# avrusbboot_example.net
KiCad netlist of a schematic drawn in EAGLE
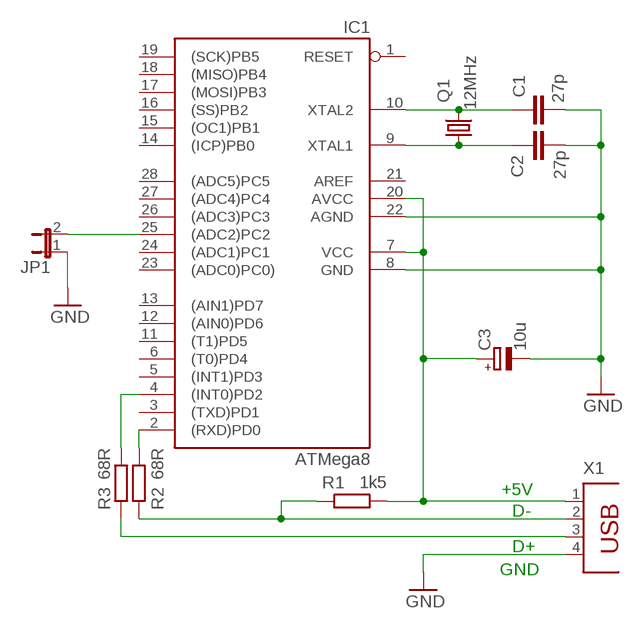
[diagram p0: schematic, sheet 1]

(export (version "E")
  (design (tool "Eeschema 10.0.6"))
  (components
    (comp (ref "C1")
      (value "27p")
      (footprint "eagle-import:C025-024X044")
      (libsource (lib "eagle-import") (part "C-EU025-024X044"))
    )
    (comp (ref "C2")
      (value "27p")
      (footprint "eagle-import:C025-024X044")
      (libsource (lib "eagle-import") (part "C-EU025-024X044"))
    )
    (comp (ref "C3")
      (value "10u")
      (footprint "eagle-import:E2,5-5")
      (libsource (lib "eagle-import") (part "CPOL-EUE2.5-5"))
    )
    (comp (ref "IC1")
      (value "ATMega8")
      (footprint "eagle-import:DIL28-3")
      (libsource (lib "eagle-import") (part "AT90S4433P"))
    )
    (comp (ref "JP1")
      (value "JP1E")
      (footprint "eagle-import:JP1")
      (libsource (lib "eagle-import") (part "JP1E"))
    )
    (comp (ref "Q1")
      (value "12MHz")
      (footprint "eagle-import:HC49_S")
      (libsource (lib "eagle-import") (part "CRYTALHC49S"))
    )
    (comp (ref "R1")
      (value "1k5")
      (footprint "eagle-import:0207_7")
      (libsource (lib "eagle-import") (part "R-EU_0207/7"))
    )
    (comp (ref "R2")
      (value "68R")
      (footprint "eagle-import:0207_7")
      (libsource (lib "eagle-import") (part "R-EU_0207/7"))
    )
    (comp (ref "R3")
      (value "68R")
      (footprint "eagle-import:0207_7")
      (libsource (lib "eagle-import") (part "R-EU_0207/7"))
    )
    (comp (ref "X1")
      (value "PN61729")
      (footprint "eagle-import:PN61729")
      (libsource (lib "eagle-import") (part "PN61729"))
    )
  )
  (nets
    (net (code "1") (name "/AREF") (class "Default")
      (node (ref "IC1") (pin "21") (pinfunction "AREF_21") (pintype "power_in"))
    )
    (net (code "2") (name "GND") (class "Default")
      (node (ref "C1") (pin "2") (pinfunction "2_2") (pintype "passive"))
      (node (ref "C2") (pin "2") (pinfunction "2_2") (pintype "passive"))
      (node (ref "C3") (pin "-") (pinfunction "-_-") (pintype "passive"))
      (node (ref "IC1") (pin "22") (pinfunction "AGND_22") (pintype "power_in"))
      (node (ref "IC1") (pin "8") (pinfunction "GND_8") (pintype "power_in"))
      (node (ref "JP1") (pin "1") (pinfunction "1_1") (pintype "passive"))
      (node (ref "X1") (pin "4") (pinfunction "4_4") (pintype "bidirectional"))
    )
    (net (code "3") (name "Net-(IC1-(ADC2)PC2)") (class "Default")
      (node (ref "IC1") (pin "25") (pinfunction "(ADC2)PC2_25") (pintype "bidirectional"))
      (node (ref "JP1") (pin "2") (pinfunction "2_2") (pintype "passive"))
    )
    (net (code "4") (name "Net-(IC1-(INT0)PD2)") (class "Default")
      (node (ref "IC1") (pin "4") (pinfunction "(INT0)PD2_4") (pintype "bidirectional"))
      (node (ref "R3") (pin "2") (pinfunction "2_2") (pintype "passive"))
    )
    (net (code "5") (name "Net-(IC1-(RXD)PD0)") (class "Default")
      (node (ref "IC1") (pin "2") (pinfunction "(RXD)PD0_2") (pintype "bidirectional"))
      (node (ref "R2") (pin "2") (pinfunction "2_2") (pintype "passive"))
    )
    (net (code "6") (name "Net-(IC1-AVCC)") (class "Default")
      (node (ref "C3") (pin "+") (pinfunction "+_+") (pintype "passive"))
      (node (ref "IC1") (pin "20") (pinfunction "AVCC_20") (pintype "power_in"))
      (node (ref "IC1") (pin "7") (pinfunction "VCC_7") (pintype "power_in"))
      (node (ref "R1") (pin "2") (pinfunction "2_2") (pintype "passive"))
      (node (ref "X1") (pin "1") (pinfunction "1_1") (pintype "bidirectional"))
    )
    (net (code "7") (name "Net-(IC1-XTAL1)") (class "Default")
      (node (ref "C2") (pin "1") (pinfunction "1_1") (pintype "passive"))
      (node (ref "IC1") (pin "9") (pinfunction "XTAL1_9") (pintype "bidirectional"))
      (node (ref "Q1") (pin "1") (pinfunction "1_1") (pintype "passive"))
    )
    (net (code "8") (name "Net-(IC1-XTAL2)") (class "Default")
      (node (ref "C1") (pin "1") (pinfunction "1_1") (pintype "passive"))
      (node (ref "IC1") (pin "10") (pinfunction "XTAL2_10") (pintype "bidirectional"))
      (node (ref "Q1") (pin "2") (pinfunction "2_2") (pintype "passive"))
    )
    (net (code "9") (name "Net-(R1-Pad1)") (class "Default")
      (node (ref "R1") (pin "1") (pinfunction "1_1") (pintype "passive"))
      (node (ref "R2") (pin "1") (pinfunction "1_1") (pintype "passive"))
      (node (ref "X1") (pin "2") (pinfunction "2_2") (pintype "bidirectional"))
    )
    (net (code "10") (name "Net-(R3-Pad1)") (class "Default")
      (node (ref "R3") (pin "1") (pinfunction "1_1") (pintype "passive"))
      (node (ref "X1") (pin "3") (pinfunction "3_3") (pintype "bidirectional"))
    )
    (net (code "11") (name "unconnected-(IC1-(ADC0)PC0)-Pad23)") (class "Default")
      (node (ref "IC1") (pin "23") (pinfunction "(ADC0)PC0)_23") (pintype "bidirectional"))
    )
    (net (code "12") (name "unconnected-(IC1-(ADC1)PC1-Pad24)") (class "Default")
      (node (ref "IC1") (pin "24") (pinfunction "(ADC1)PC1_24") (pintype "bidirectional"))
    )
    (net (code "13") (name "unconnected-(IC1-(ADC3)PC3-Pad26)") (class "Default")
      (node (ref "IC1") (pin "26") (pinfunction "(ADC3)PC3_26") (pintype "bidirectional"))
    )
    (net (code "14") (name "unconnected-(IC1-(ADC4)PC4-Pad27)") (class "Default")
      (node (ref "IC1") (pin "27") (pinfunction "(ADC4)PC4_27") (pintype "bidirectional"))
    )
    (net (code "15") (name "unconnected-(IC1-(ADC5)PC5-Pad28)") (class "Default")
      (node (ref "IC1") (pin "28") (pinfunction "(ADC5)PC5_28") (pintype "bidirectional"))
    )
    (net (code "16") (name "unconnected-(IC1-(AIN0)PD6-Pad12)") (class "Default")
      (node (ref "IC1") (pin "12") (pinfunction "(AIN0)PD6_12") (pintype "bidirectional"))
    )
    (net (code "17") (name "unconnected-(IC1-(AIN1)PD7-Pad13)") (class "Default")
      (node (ref "IC1") (pin "13") (pinfunction "(AIN1)PD7_13") (pintype "bidirectional"))
    )
    (net (code "18") (name "unconnected-(IC1-(ICP)PB0-Pad14)") (class "Default")
      (node (ref "IC1") (pin "14") (pinfunction "(ICP)PB0_14") (pintype "bidirectional"))
    )
    (net (code "19") (name "unconnected-(IC1-(INT1)PD3-Pad5)") (class "Default")
      (node (ref "IC1") (pin "5") (pinfunction "(INT1)PD3_5") (pintype "bidirectional"))
    )
    (net (code "20") (name "unconnected-(IC1-(MISO)PB4-Pad18)") (class "Default")
      (node (ref "IC1") (pin "18") (pinfunction "(MISO)PB4_18") (pintype "bidirectional"))
    )
    (net (code "21") (name "unconnected-(IC1-(MOSI)PB3-Pad17)") (class "Default")
      (node (ref "IC1") (pin "17") (pinfunction "(MOSI)PB3_17") (pintype "bidirectional"))
    )
    (net (code "22") (name "unconnected-(IC1-(OC1)PB1-Pad15)") (class "Default")
      (node (ref "IC1") (pin "15") (pinfunction "(OC1)PB1_15") (pintype "bidirectional"))
    )
    (net (code "23") (name "unconnected-(IC1-(SCK)PB5-Pad19)") (class "Default")
      (node (ref "IC1") (pin "19") (pinfunction "(SCK)PB5_19") (pintype "bidirectional"))
    )
    (net (code "24") (name "unconnected-(IC1-(SS)PB2-Pad16)") (class "Default")
      (node (ref "IC1") (pin "16") (pinfunction "(SS)PB2_16") (pintype "bidirectional"))
    )
    (net (code "25") (name "unconnected-(IC1-(T0)PD4-Pad6)") (class "Default")
      (node (ref "IC1") (pin "6") (pinfunction "(T0)PD4_6") (pintype "bidirectional"))
    )
    (net (code "26") (name "unconnected-(IC1-(T1)PD5-Pad11)") (class "Default")
      (node (ref "IC1") (pin "11") (pinfunction "(T1)PD5_11") (pintype "bidirectional"))
    )
    (net (code "27") (name "unconnected-(IC1-(TXD)PD1-Pad3)") (class "Default")
      (node (ref "IC1") (pin "3") (pinfunction "(TXD)PD1_3") (pintype "bidirectional"))
    )
    (net (code "28") (name "unconnected-(IC1-RESET-Pad1)") (class "Default")
      (node (ref "IC1") (pin "1") (pinfunction "RESET_1") (pintype "input"))
    )
  )
)
